# v8_engine.net
KiCad netlist of a schematic drawn in EAGLE
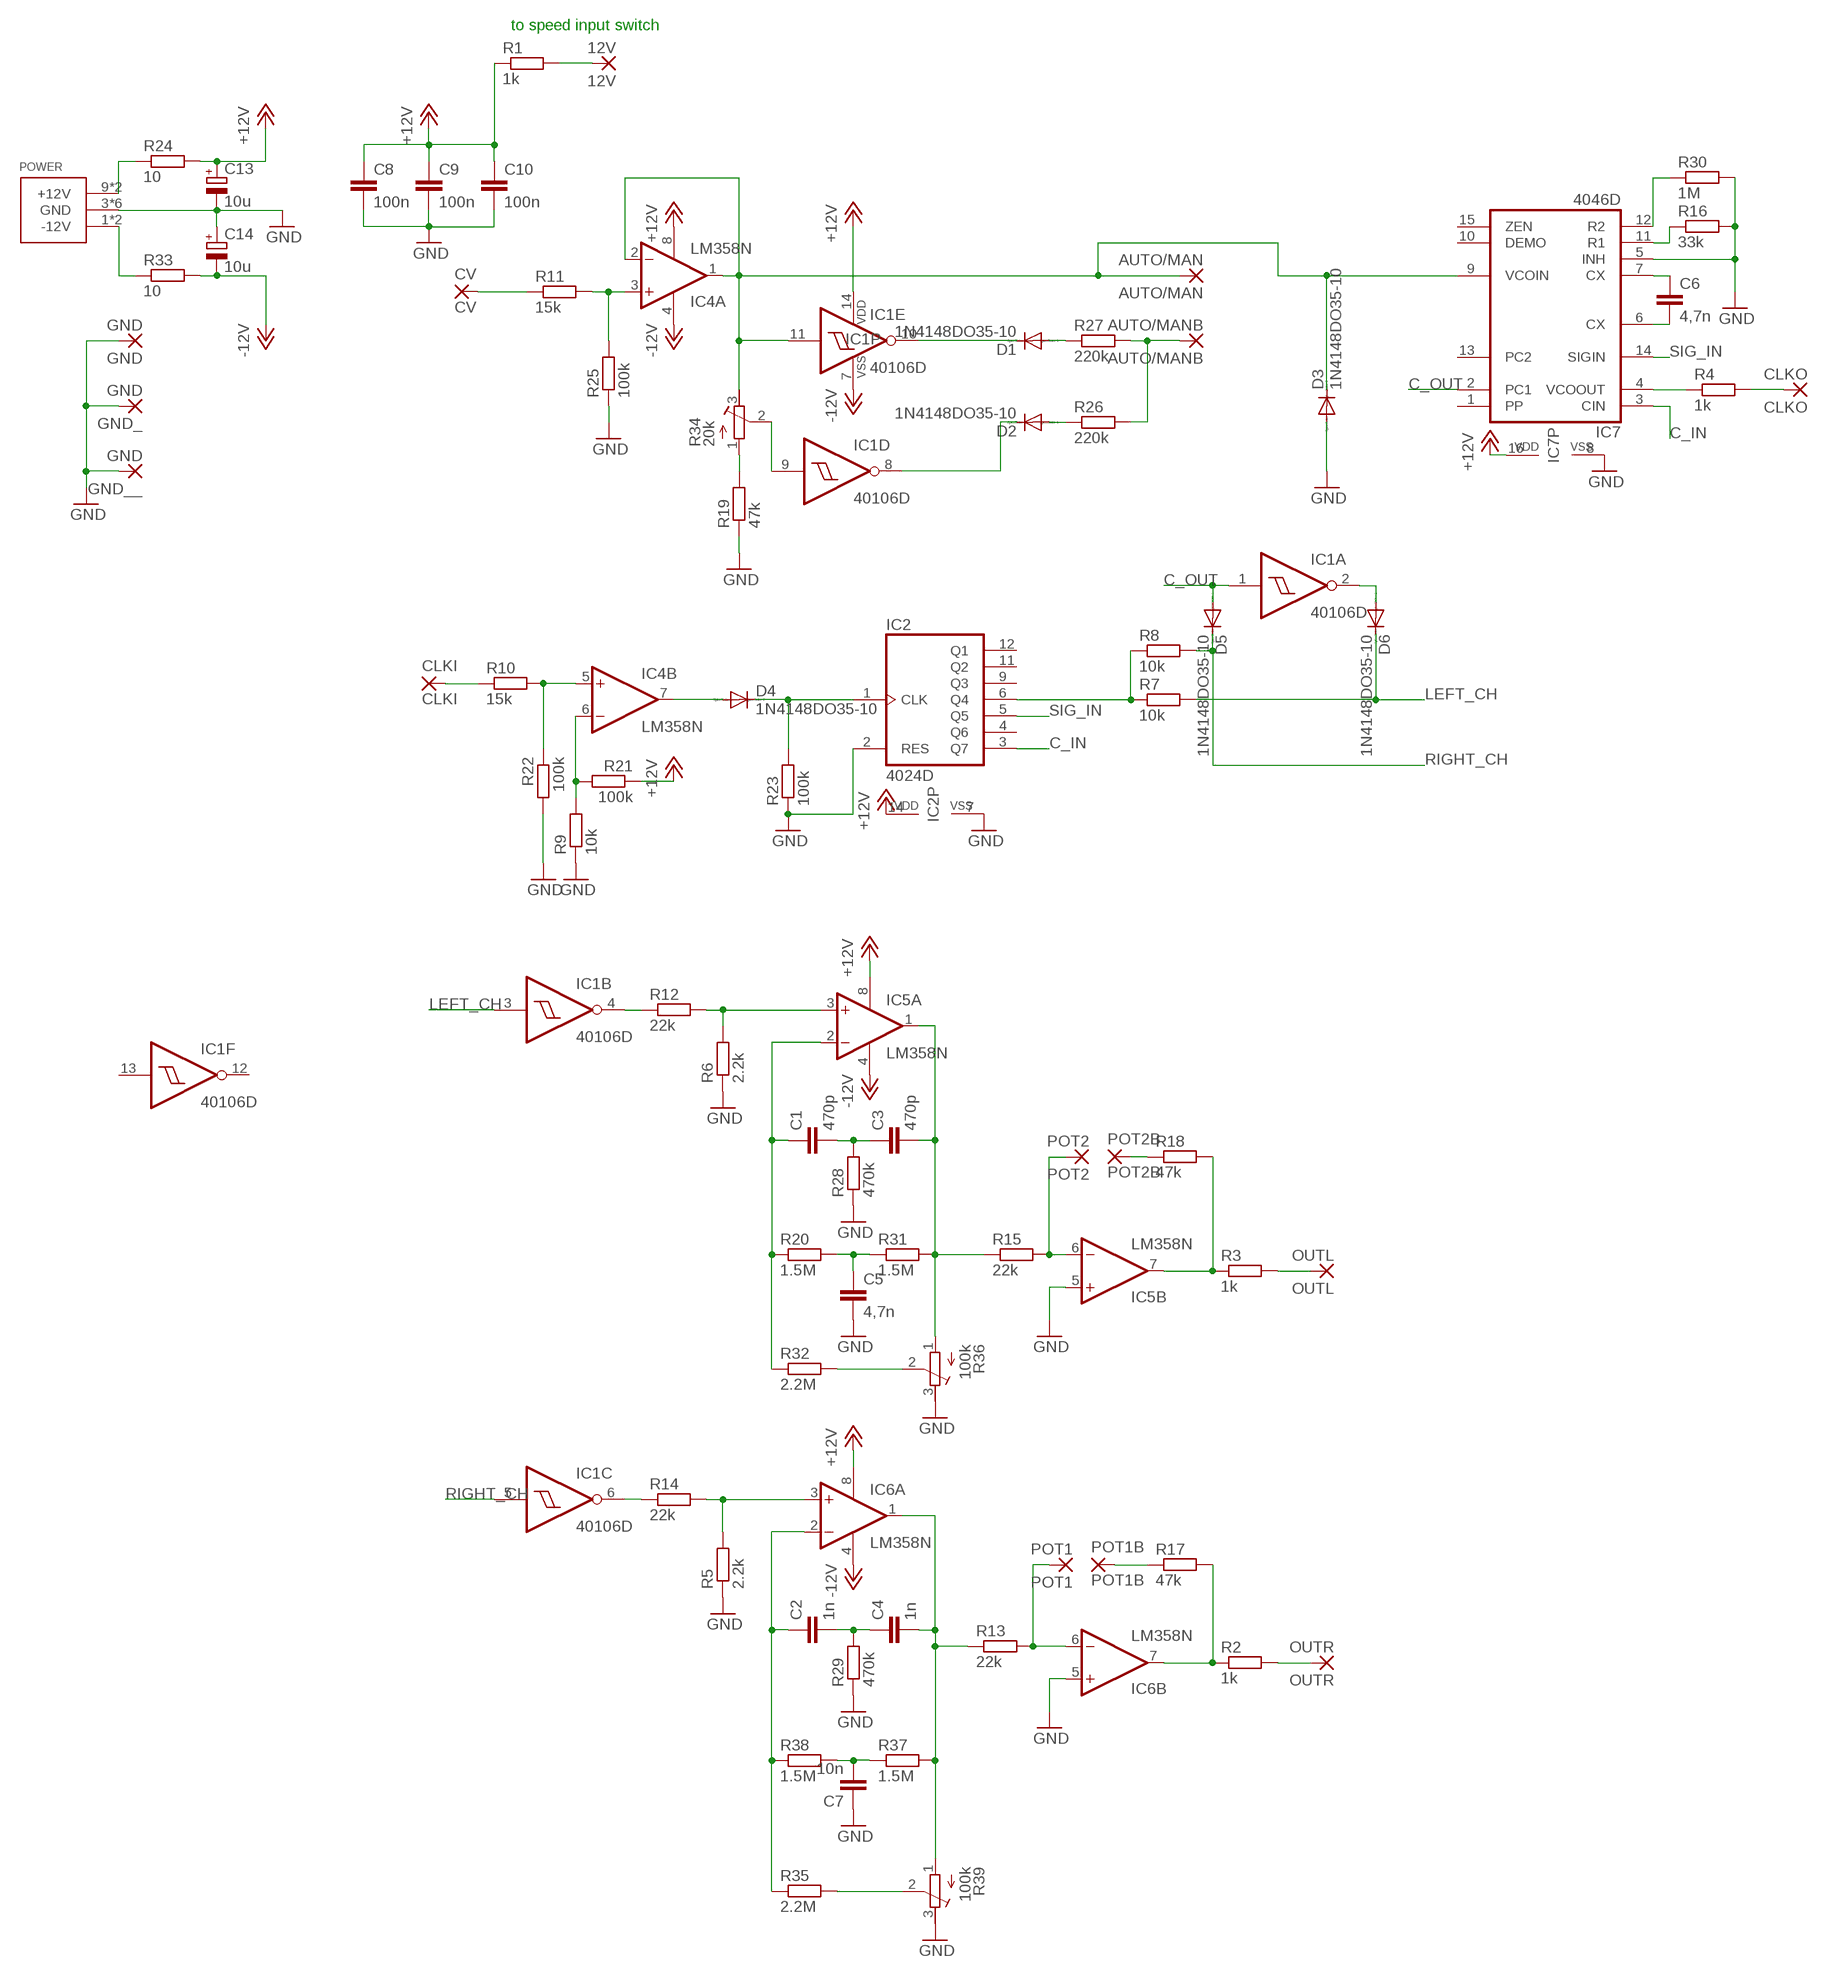
[diagram p0: schematic, sheet 1]

(export (version "E")
  (design (tool "Eeschema 10.0.6"))
  (components
    (comp (ref "12V")
      (value "12V")
      (footprint "eagle-import:1,6_0,9")
      (libsource (lib "eagle-import") (part "1,6/0,9"))
    )
    (comp (ref "AUTO/MAN")
      (value "AUTO/MAN")
      (footprint "eagle-import:1,6_0,9")
      (libsource (lib "eagle-import") (part "1,6/0,9"))
    )
    (comp (ref "AUTO/MANB")
      (value "AUTO/MANB")
      (footprint "eagle-import:1,6_0,9")
      (libsource (lib "eagle-import") (part "1,6/0,9"))
    )
    (comp (ref "C1")
      (value "470p")
      (footprint "eagle-import:C050-025X075")
      (libsource (lib "eagle-import") (part "C-EU050-025X075"))
    )
    (comp (ref "C2")
      (value "1n")
      (footprint "eagle-import:C050-025X075")
      (libsource (lib "eagle-import") (part "C-EU050-025X075"))
    )
    (comp (ref "C3")
      (value "470p")
      (footprint "eagle-import:C050-025X075")
      (libsource (lib "eagle-import") (part "C-EU050-025X075"))
    )
    (comp (ref "C4")
      (value "1n")
      (footprint "eagle-import:C050-025X075")
      (libsource (lib "eagle-import") (part "C-EU050-025X075"))
    )
    (comp (ref "C5")
      (value "4,7n")
      (footprint "eagle-import:C050-025X075")
      (libsource (lib "eagle-import") (part "C-EU050-025X075"))
    )
    (comp (ref "C6")
      (value "4,7n")
      (footprint "eagle-import:C050-025X075")
      (libsource (lib "eagle-import") (part "C-EU050-025X075"))
    )
    (comp (ref "C7")
      (value "10n")
      (footprint "eagle-import:C050-025X075")
      (libsource (lib "eagle-import") (part "C-EU050-025X075"))
    )
    (comp (ref "C8")
      (value "100n")
      (footprint "eagle-import:C050-025X075")
      (libsource (lib "eagle-import") (part "C-EU050-025X075"))
    )
    (comp (ref "C9")
      (value "100n")
      (footprint "eagle-import:C050-025X075")
      (libsource (lib "eagle-import") (part "C-EU050-025X075"))
    )
    (comp (ref "C10")
      (value "100n")
      (footprint "eagle-import:C050-025X075")
      (libsource (lib "eagle-import") (part "C-EU050-025X075"))
    )
    (comp (ref "C13")
      (value "10u")
      (footprint "eagle-import:E2,5-6")
      (libsource (lib "eagle-import") (part "CPOL-EUE2.5-6"))
    )
    (comp (ref "C14")
      (value "10u")
      (footprint "eagle-import:E2,5-6")
      (libsource (lib "eagle-import") (part "CPOL-EUE2.5-6"))
    )
    (comp (ref "CLKI")
      (value "CLKI")
      (footprint "eagle-import:1,6_0,9")
      (libsource (lib "eagle-import") (part "1,6/0,9"))
    )
    (comp (ref "CLKO")
      (value "CLKO")
      (footprint "eagle-import:1,6_0,9")
      (libsource (lib "eagle-import") (part "1,6/0,9"))
    )
    (comp (ref "CV")
      (value "CV")
      (footprint "eagle-import:1,6_0,9")
      (libsource (lib "eagle-import") (part "1,6/0,9"))
    )
    (comp (ref "D1")
      (value "1N4148DO35-10")
      (footprint "eagle-import:DO35-10")
      (libsource (lib "eagle-import") (part "1N4148DO35-10"))
    )
    (comp (ref "D2")
      (value "1N4148DO35-10")
      (footprint "eagle-import:DO35-10")
      (libsource (lib "eagle-import") (part "1N4148DO35-10"))
    )
    (comp (ref "D3")
      (value "1N4148DO35-10")
      (footprint "eagle-import:DO35-10")
      (libsource (lib "eagle-import") (part "1N4148DO35-10"))
    )
    (comp (ref "D4")
      (value "1N4148DO35-10")
      (footprint "eagle-import:DO35-10")
      (libsource (lib "eagle-import") (part "1N4148DO35-10"))
    )
    (comp (ref "D5")
      (value "1N4148DO35-10")
      (footprint "eagle-import:DO35-10")
      (libsource (lib "eagle-import") (part "1N4148DO35-10"))
    )
    (comp (ref "D6")
      (value "1N4148DO35-10")
      (footprint "eagle-import:DO35-10")
      (libsource (lib "eagle-import") (part "1N4148DO35-10"))
    )
    (comp (ref "GND")
      (value "GND")
      (footprint "eagle-import:1,6_0,9")
      (libsource (lib "eagle-import") (part "1,6/0,9"))
    )
    (comp (ref "GND_")
      (value "GND")
      (footprint "eagle-import:1,6_0,9")
      (libsource (lib "eagle-import") (part "1,6/0,9"))
    )
    (comp (ref "GND__")
      (value "GND")
      (footprint "eagle-import:1,6_0,9")
      (libsource (lib "eagle-import") (part "1,6/0,9"))
    )
    (comp (ref "IC1")
      (value "40106D")
      (footprint "eagle-import:SO14")
      (libsource (lib "eagle-import") (part "40106D"))
    )
    (comp (ref "IC2")
      (value "4024D")
      (footprint "eagle-import:SO14")
      (libsource (lib "eagle-import") (part "4024D"))
    )
    (comp (ref "IC4")
      (value "LM358N")
      (footprint "eagle-import:DIL08")
      (libsource (lib "eagle-import") (part "LM358N"))
    )
    (comp (ref "IC5")
      (value "LM358N")
      (footprint "eagle-import:DIL08")
      (libsource (lib "eagle-import") (part "LM358N"))
    )
    (comp (ref "IC6")
      (value "LM358N")
      (footprint "eagle-import:DIL08")
      (libsource (lib "eagle-import") (part "LM358N"))
    )
    (comp (ref "IC7")
      (value "4046D")
      (footprint "eagle-import:SO16")
      (libsource (lib "eagle-import") (part "4046D"))
    )
    (comp (ref "OUTL")
      (value "OUTL")
      (footprint "eagle-import:1,6_0,9")
      (libsource (lib "eagle-import") (part "1,6/0,9"))
    )
    (comp (ref "OUTR")
      (value "OUTR")
      (footprint "eagle-import:1,6_0,9")
      (libsource (lib "eagle-import") (part "1,6/0,9"))
    )
    (comp (ref "POT1")
      (value "POT1")
      (footprint "eagle-import:1,6_0,9")
      (libsource (lib "eagle-import") (part "1,6/0,9"))
    )
    (comp (ref "POT1B")
      (value "POT1B")
      (footprint "eagle-import:1,6_0,9")
      (libsource (lib "eagle-import") (part "1,6/0,9"))
    )
    (comp (ref "POT2")
      (value "POT2")
      (footprint "eagle-import:1,6_0,9")
      (libsource (lib "eagle-import") (part "1,6/0,9"))
    )
    (comp (ref "POT2B")
      (value "POT2B")
      (footprint "eagle-import:1,6_0,9")
      (libsource (lib "eagle-import") (part "1,6/0,9"))
    )
    (comp (ref "POWER")
      (value "POWER_SIMPLE10")
      (footprint "eagle-import:POWER_10")
      (libsource (lib "eagle-import") (part "POWER_SIMPLE10"))
    )
    (comp (ref "R1")
      (value "1k")
      (footprint "eagle-import:0207_10")
      (libsource (lib "eagle-import") (part "R-EU_0207/10"))
    )
    (comp (ref "R2")
      (value "1k")
      (footprint "eagle-import:0207_10")
      (libsource (lib "eagle-import") (part "R-EU_0207/10"))
    )
    (comp (ref "R3")
      (value "1k")
      (footprint "eagle-import:0207_10")
      (libsource (lib "eagle-import") (part "R-EU_0207/10"))
    )
    (comp (ref "R4")
      (value "1k")
      (footprint "eagle-import:0207_10")
      (libsource (lib "eagle-import") (part "R-EU_0207/10"))
    )
    (comp (ref "R5")
      (value "2.2k")
      (footprint "eagle-import:0207_10")
      (libsource (lib "eagle-import") (part "R-EU_0207/10"))
    )
    (comp (ref "R6")
      (value "2.2k")
      (footprint "eagle-import:0207_10")
      (libsource (lib "eagle-import") (part "R-EU_0207/10"))
    )
    (comp (ref "R7")
      (value "10k")
      (footprint "eagle-import:0207_10")
      (libsource (lib "eagle-import") (part "R-EU_0207/10"))
    )
    (comp (ref "R8")
      (value "10k")
      (footprint "eagle-import:0207_10")
      (libsource (lib "eagle-import") (part "R-EU_0207/10"))
    )
    (comp (ref "R9")
      (value "10k")
      (footprint "eagle-import:0207_10")
      (libsource (lib "eagle-import") (part "R-EU_0207/10"))
    )
    (comp (ref "R10")
      (value "15k")
      (footprint "eagle-import:0207_10")
      (libsource (lib "eagle-import") (part "R-EU_0207/10"))
    )
    (comp (ref "R11")
      (value "15k")
      (footprint "eagle-import:0207_10")
      (libsource (lib "eagle-import") (part "R-EU_0207/10"))
    )
    (comp (ref "R12")
      (value "22k")
      (footprint "eagle-import:0207_10")
      (libsource (lib "eagle-import") (part "R-EU_0207/10"))
    )
    (comp (ref "R13")
      (value "22k")
      (footprint "eagle-import:0207_10")
      (libsource (lib "eagle-import") (part "R-EU_0207/10"))
    )
    (comp (ref "R14")
      (value "22k")
      (footprint "eagle-import:0207_10")
      (libsource (lib "eagle-import") (part "R-EU_0207/10"))
    )
    (comp (ref "R15")
      (value "22k")
      (footprint "eagle-import:0207_10")
      (libsource (lib "eagle-import") (part "R-EU_0207/10"))
    )
    (comp (ref "R16")
      (value "33k")
      (footprint "eagle-import:0207_10")
      (libsource (lib "eagle-import") (part "R-EU_0207/10"))
    )
    (comp (ref "R17")
      (value "47k")
      (footprint "eagle-import:0207_10")
      (libsource (lib "eagle-import") (part "R-EU_0207/10"))
    )
    (comp (ref "R18")
      (value "47k")
      (footprint "eagle-import:0207_10")
      (libsource (lib "eagle-import") (part "R-EU_0207/10"))
    )
    (comp (ref "R19")
      (value "47k")
      (footprint "eagle-import:0207_10")
      (libsource (lib "eagle-import") (part "R-EU_0207/10"))
    )
    (comp (ref "R20")
      (value "1.5M")
      (footprint "eagle-import:0207_10")
      (libsource (lib "eagle-import") (part "R-EU_0207/10"))
    )
    (comp (ref "R21")
      (value "100k")
      (footprint "eagle-import:0207_10")
      (libsource (lib "eagle-import") (part "R-EU_0207/10"))
    )
    (comp (ref "R22")
      (value "100k")
      (footprint "eagle-import:0207_10")
      (libsource (lib "eagle-import") (part "R-EU_0207/10"))
    )
    (comp (ref "R23")
      (value "100k")
      (footprint "eagle-import:0207_10")
      (libsource (lib "eagle-import") (part "R-EU_0207/10"))
    )
    (comp (ref "R24")
      (value "10")
      (footprint "eagle-import:0207_10")
      (libsource (lib "eagle-import") (part "R-EU_0207/10"))
    )
    (comp (ref "R25")
      (value "100k")
      (footprint "eagle-import:0207_10")
      (libsource (lib "eagle-import") (part "R-EU_0207/10"))
    )
    (comp (ref "R26")
      (value "220k")
      (footprint "eagle-import:0207_10")
      (libsource (lib "eagle-import") (part "R-EU_0207/10"))
    )
    (comp (ref "R27")
      (value "220k")
      (footprint "eagle-import:0207_10")
      (libsource (lib "eagle-import") (part "R-EU_0207/10"))
    )
    (comp (ref "R28")
      (value "470k")
      (footprint "eagle-import:0207_10")
      (libsource (lib "eagle-import") (part "R-EU_0207/10"))
    )
    (comp (ref "R29")
      (value "470k")
      (footprint "eagle-import:0207_10")
      (libsource (lib "eagle-import") (part "R-EU_0207/10"))
    )
    (comp (ref "R30")
      (value "1M")
      (footprint "eagle-import:0207_10")
      (libsource (lib "eagle-import") (part "R-EU_0207/10"))
    )
    (comp (ref "R31")
      (value "1.5M")
      (footprint "eagle-import:0207_10")
      (libsource (lib "eagle-import") (part "R-EU_0207/10"))
    )
    (comp (ref "R32")
      (value "2.2M")
      (footprint "eagle-import:0207_10")
      (libsource (lib "eagle-import") (part "R-EU_0207/10"))
    )
    (comp (ref "R33")
      (value "10")
      (footprint "eagle-import:0207_10")
      (libsource (lib "eagle-import") (part "R-EU_0207/10"))
    )
    (comp (ref "R34")
      (value "20k")
      (footprint "eagle-import:RTRIM3339P")
      (libsource (lib "eagle-import") (part "R-TRIMM3339P"))
    )
    (comp (ref "R35")
      (value "2.2M")
      (footprint "eagle-import:0207_10")
      (libsource (lib "eagle-import") (part "R-EU_0207/10"))
    )
    (comp (ref "R36")
      (value "100k")
      (footprint "eagle-import:RTRIM3339P")
      (libsource (lib "eagle-import") (part "R-TRIMM3339P"))
    )
    (comp (ref "R37")
      (value "1.5M")
      (footprint "eagle-import:0207_10")
      (libsource (lib "eagle-import") (part "R-EU_0207/10"))
    )
    (comp (ref "R38")
      (value "1.5M")
      (footprint "eagle-import:0207_10")
      (libsource (lib "eagle-import") (part "R-EU_0207/10"))
    )
    (comp (ref "R39")
      (value "100k")
      (footprint "eagle-import:RTRIM3339P")
      (libsource (lib "eagle-import") (part "R-TRIMM3339P"))
    )
  )
  (nets
    (net (code "1") (name "+12V") (class "Default")
      (node (ref "C10") (pin "1") (pinfunction "1_1") (pintype "passive"))
      (node (ref "C13") (pin "+") (pinfunction "+_+") (pintype "passive"))
      (node (ref "C8") (pin "1") (pinfunction "1_1") (pintype "passive"))
      (node (ref "C9") (pin "1") (pinfunction "1_1") (pintype "passive"))
      (node (ref "IC1") (pin "14") (pinfunction "VDD_14") (pintype "power_in"))
      (node (ref "IC2") (pin "14") (pinfunction "VDD_14") (pintype "power_in"))
      (node (ref "IC4") (pin "8") (pinfunction "V+_8") (pintype "power_in"))
      (node (ref "IC5") (pin "8") (pinfunction "V+_8") (pintype "power_in"))
      (node (ref "IC6") (pin "8") (pinfunction "V+_8") (pintype "power_in"))
      (node (ref "IC7") (pin "16") (pinfunction "VDD_16") (pintype "power_in"))
      (node (ref "R1") (pin "1") (pinfunction "1_1") (pintype "passive"))
      (node (ref "R21") (pin "1") (pinfunction "1_1") (pintype "passive"))
      (node (ref "R24") (pin "2") (pinfunction "2_2") (pintype "passive"))
    )
    (net (code "2") (name "-12V") (class "Default")
      (node (ref "C14") (pin "-") (pinfunction "-_-") (pintype "passive"))
      (node (ref "IC1") (pin "7") (pinfunction "VSS_7") (pintype "power_in"))
      (node (ref "IC4") (pin "4") (pinfunction "V-_4") (pintype "power_in"))
      (node (ref "IC5") (pin "4") (pinfunction "V-_4") (pintype "power_in"))
      (node (ref "IC6") (pin "4") (pinfunction "V-_4") (pintype "power_in"))
      (node (ref "R33") (pin "2") (pinfunction "2_2") (pintype "passive"))
    )
    (net (code "3") (name "/C_IN") (class "Default")
      (node (ref "IC2") (pin "3") (pinfunction "Q7_3") (pintype "output"))
      (node (ref "IC7") (pin "3") (pinfunction "CIN_3") (pintype "input"))
    )
    (net (code "4") (name "/C_OUT") (class "Default")
      (node (ref "D5") (pin "A") (pinfunction "A_A") (pintype "passive"))
      (node (ref "IC1") (pin "1") (pinfunction "I_1") (pintype "input"))
      (node (ref "IC7") (pin "2") (pinfunction "PC1_2") (pintype "output"))
    )
    (net (code "5") (name "/LEFT_CH") (class "Default")
      (node (ref "D6") (pin "C") (pinfunction "C_C") (pintype "passive"))
      (node (ref "IC1") (pin "3") (pinfunction "I_3") (pintype "input"))
      (node (ref "R7") (pin "2") (pinfunction "2_2") (pintype "passive"))
    )
    (net (code "6") (name "/RIGHT_CH") (class "Default")
      (node (ref "D5") (pin "C") (pinfunction "C_C") (pintype "passive"))
      (node (ref "IC1") (pin "5") (pinfunction "I_5") (pintype "input"))
      (node (ref "R8") (pin "2") (pinfunction "2_2") (pintype "passive"))
    )
    (net (code "7") (name "/SIG_IN") (class "Default")
      (node (ref "IC2") (pin "5") (pinfunction "Q5_5") (pintype "output"))
      (node (ref "IC7") (pin "14") (pinfunction "SIGIN_14") (pintype "input"))
    )
    (net (code "8") (name "GND") (class "Default")
      (node (ref "C10") (pin "2") (pinfunction "2_2") (pintype "passive"))
      (node (ref "C13") (pin "-") (pinfunction "-_-") (pintype "passive"))
      (node (ref "C14") (pin "+") (pinfunction "+_+") (pintype "passive"))
      (node (ref "C5") (pin "2") (pinfunction "2_2") (pintype "passive"))
      (node (ref "C7") (pin "1") (pinfunction "1_1") (pintype "passive"))
      (node (ref "C8") (pin "2") (pinfunction "2_2") (pintype "passive"))
      (node (ref "C9") (pin "2") (pinfunction "2_2") (pintype "passive"))
      (node (ref "D3") (pin "A") (pinfunction "A_A") (pintype "passive"))
      (node (ref "GND") (pin "1") (pinfunction "P_1") (pintype "passive"))
      (node (ref "GND_") (pin "1") (pinfunction "P_1") (pintype "passive"))
      (node (ref "GND__") (pin "1") (pinfunction "P_1") (pintype "passive"))
      (node (ref "IC2") (pin "2") (pinfunction "RES_2") (pintype "input"))
      (node (ref "IC2") (pin "7") (pinfunction "VSS_7") (pintype "power_in"))
      (node (ref "IC5") (pin "5") (pinfunction "+IN_5") (pintype "input"))
      (node (ref "IC6") (pin "5") (pinfunction "+IN_5") (pintype "input"))
      (node (ref "IC7") (pin "5") (pinfunction "INH_5") (pintype "input"))
      (node (ref "IC7") (pin "8") (pinfunction "VSS_8") (pintype "power_in"))
      (node (ref "POWER") (pin "3") (pinfunction "GND_3") (pintype "bidirectional"))
      (node (ref "POWER") (pin "4") (pinfunction "GND_4") (pintype "bidirectional"))
      (node (ref "POWER") (pin "5") (pinfunction "GND_5") (pintype "bidirectional"))
      (node (ref "POWER") (pin "6") (pinfunction "GND_6") (pintype "bidirectional"))
      (node (ref "POWER") (pin "7") (pinfunction "GND_7") (pintype "bidirectional"))
      (node (ref "POWER") (pin "8") (pinfunction "GND_8") (pintype "bidirectional"))
      (node (ref "R16") (pin "2") (pinfunction "2_2") (pintype "passive"))
      (node (ref "R19") (pin "1") (pinfunction "1_1") (pintype "passive"))
      (node (ref "R22") (pin "2") (pinfunction "2_2") (pintype "passive"))
      (node (ref "R23") (pin "1") (pinfunction "1_1") (pintype "passive"))
      (node (ref "R25") (pin "1") (pinfunction "1_1") (pintype "passive"))
      (node (ref "R28") (pin "1") (pinfunction "1_1") (pintype "passive"))
      (node (ref "R29") (pin "1") (pinfunction "1_1") (pintype "passive"))
      (node (ref "R30") (pin "2") (pinfunction "2_2") (pintype "passive"))
      (node (ref "R36") (pin "3") (pinfunction "E_3") (pintype "passive"))
      (node (ref "R39") (pin "3") (pinfunction "E_3") (pintype "passive"))
      (node (ref "R5") (pin "1") (pinfunction "1_1") (pintype "passive"))
      (node (ref "R6") (pin "1") (pinfunction "1_1") (pintype "passive"))
      (node (ref "R9") (pin "1") (pinfunction "1_1") (pintype "passive"))
    )
    (net (code "9") (name "Net-(12V-P)") (class "Default")
      (node (ref "12V") (pin "1") (pinfunction "P_1") (pintype "passive"))
      (node (ref "R1") (pin "2") (pinfunction "2_2") (pintype "passive"))
    )
    (net (code "10") (name "Net-(AUTO/MAN-P)") (class "Default")
      (node (ref "AUTO/MAN") (pin "1") (pinfunction "P_1") (pintype "passive"))
      (node (ref "D3") (pin "C") (pinfunction "C_C") (pintype "passive"))
      (node (ref "IC1") (pin "11") (pinfunction "I_11") (pintype "input"))
      (node (ref "IC4") (pin "1") (pinfunction "OUT_1") (pintype "output"))
      (node (ref "IC4") (pin "2") (pinfunction "-IN_2") (pintype "input"))
      (node (ref "IC7") (pin "9") (pinfunction "VCOIN_9") (pintype "input"))
      (node (ref "R34") (pin "3") (pinfunction "E_3") (pintype "passive"))
    )
    (net (code "11") (name "Net-(AUTO/MANB-P)") (class "Default")
      (node (ref "AUTO/MANB") (pin "1") (pinfunction "P_1") (pintype "passive"))
      (node (ref "R26") (pin "2") (pinfunction "2_2") (pintype "passive"))
      (node (ref "R27") (pin "2") (pinfunction "2_2") (pintype "passive"))
    )
    (net (code "12") (name "Net-(C1-Pad2)") (class "Default")
      (node (ref "C1") (pin "2") (pinfunction "2_2") (pintype "passive"))
      (node (ref "C3") (pin "1") (pinfunction "1_1") (pintype "passive"))
      (node (ref "R28") (pin "2") (pinfunction "2_2") (pintype "passive"))
    )
    (net (code "13") (name "Net-(C2-Pad2)") (class "Default")
      (node (ref "C2") (pin "2") (pinfunction "2_2") (pintype "passive"))
      (node (ref "C4") (pin "1") (pinfunction "1_1") (pintype "passive"))
      (node (ref "R29") (pin "2") (pinfunction "2_2") (pintype "passive"))
    )
    (net (code "14") (name "Net-(C5-Pad1)") (class "Default")
      (node (ref "C5") (pin "1") (pinfunction "1_1") (pintype "passive"))
      (node (ref "R20") (pin "2") (pinfunction "2_2") (pintype "passive"))
      (node (ref "R31") (pin "1") (pinfunction "1_1") (pintype "passive"))
    )
    (net (code "15") (name "Net-(C6-Pad1)") (class "Default")
      (node (ref "C6") (pin "1") (pinfunction "1_1") (pintype "passive"))
      (node (ref "IC7") (pin "7") (pinfunction "CX_7") (pintype "input"))
    )
    (net (code "16") (name "Net-(C6-Pad2)") (class "Default")
      (node (ref "C6") (pin "2") (pinfunction "2_2") (pintype "passive"))
      (node (ref "IC7") (pin "6") (pinfunction "CX_6") (pintype "input"))
    )
    (net (code "17") (name "Net-(C7-Pad2)") (class "Default")
      (node (ref "C7") (pin "2") (pinfunction "2_2") (pintype "passive"))
      (node (ref "R37") (pin "1") (pinfunction "1_1") (pintype "passive"))
      (node (ref "R38") (pin "2") (pinfunction "2_2") (pintype "passive"))
    )
    (net (code "18") (name "Net-(CLKI-P)") (class "Default")
      (node (ref "CLKI") (pin "1") (pinfunction "P_1") (pintype "passive"))
      (node (ref "R10") (pin "1") (pinfunction "1_1") (pintype "passive"))
    )
    (net (code "19") (name "Net-(CLKO-P)") (class "Default")
      (node (ref "CLKO") (pin "1") (pinfunction "P_1") (pintype "passive"))
      (node (ref "R4") (pin "2") (pinfunction "2_2") (pintype "passive"))
    )
    (net (code "20") (name "Net-(CV-P)") (class "Default")
      (node (ref "CV") (pin "1") (pinfunction "P_1") (pintype "passive"))
      (node (ref "R11") (pin "1") (pinfunction "1_1") (pintype "passive"))
    )
    (net (code "21") (name "Net-(D1-PadA)") (class "Default")
      (node (ref "D1") (pin "A") (pinfunction "A_A") (pintype "passive"))
      (node (ref "R27") (pin "1") (pinfunction "1_1") (pintype "passive"))
    )
    (net (code "22") (name "Net-(D2-PadA)") (class "Default")
      (node (ref "D2") (pin "A") (pinfunction "A_A") (pintype "passive"))
      (node (ref "R26") (pin "1") (pinfunction "1_1") (pintype "passive"))
    )
    (net (code "23") (name "Net-(IC1A-O)") (class "Default")
      (node (ref "D6") (pin "A") (pinfunction "A_A") (pintype "passive"))
      (node (ref "IC1") (pin "2") (pinfunction "O_2") (pintype "output"))
    )
    (net (code "24") (name "Net-(IC1B-O)") (class "Default")
      (node (ref "IC1") (pin "4") (pinfunction "O_4") (pintype "output"))
      (node (ref "R12") (pin "1") (pinfunction "1_1") (pintype "passive"))
    )
    (net (code "25") (name "Net-(IC1C-O)") (class "Default")
      (node (ref "IC1") (pin "6") (pinfunction "O_6") (pintype "output"))
      (node (ref "R14") (pin "1") (pinfunction "1_1") (pintype "passive"))
    )
    (net (code "26") (name "Net-(IC1D-I)") (class "Default")
      (node (ref "IC1") (pin "9") (pinfunction "I_9") (pintype "input"))
      (node (ref "R34") (pin "2") (pinfunction "S_2") (pintype "passive"))
    )
    (net (code "27") (name "Net-(IC1D-O)") (class "Default")
      (node (ref "D2") (pin "C") (pinfunction "C_C") (pintype "passive"))
      (node (ref "IC1") (pin "8") (pinfunction "O_8") (pintype "output"))
    )
    (net (code "28") (name "Net-(IC1E-O)") (class "Default")
      (node (ref "D1") (pin "C") (pinfunction "C_C") (pintype "passive"))
      (node (ref "IC1") (pin "10") (pinfunction "O_10") (pintype "output"))
    )
    (net (code "29") (name "Net-(IC2A-CLK)") (class "Default")
      (node (ref "D4") (pin "C") (pinfunction "C_C") (pintype "passive"))
      (node (ref "IC2") (pin "1") (pinfunction "CLK_1") (pintype "input"))
      (node (ref "R23") (pin "2") (pinfunction "2_2") (pintype "passive"))
    )
    (net (code "30") (name "Net-(IC2A-Q4)") (class "Default")
      (node (ref "IC2") (pin "6") (pinfunction "Q4_6") (pintype "output"))
      (node (ref "R7") (pin "1") (pinfunction "1_1") (pintype "passive"))
      (node (ref "R8") (pin "1") (pinfunction "1_1") (pintype "passive"))
    )
    (net (code "31") (name "Net-(IC4A-+IN)") (class "Default")
      (node (ref "IC4") (pin "3") (pinfunction "+IN_3") (pintype "input"))
      (node (ref "R11") (pin "2") (pinfunction "2_2") (pintype "passive"))
      (node (ref "R25") (pin "2") (pinfunction "2_2") (pintype "passive"))
    )
    (net (code "32") (name "Net-(IC4B-+IN)") (class "Default")
      (node (ref "IC4") (pin "5") (pinfunction "+IN_5") (pintype "input"))
      (node (ref "R10") (pin "2") (pinfunction "2_2") (pintype "passive"))
      (node (ref "R22") (pin "1") (pinfunction "1_1") (pintype "passive"))
    )
    (net (code "33") (name "Net-(IC4B--IN)") (class "Default")
      (node (ref "IC4") (pin "6") (pinfunction "-IN_6") (pintype "input"))
      (node (ref "R21") (pin "2") (pinfunction "2_2") (pintype "passive"))
      (node (ref "R9") (pin "2") (pinfunction "2_2") (pintype "passive"))
    )
    (net (code "34") (name "Net-(IC4B-OUT)") (class "Default")
      (node (ref "D4") (pin "A") (pinfunction "A_A") (pintype "passive"))
      (node (ref "IC4") (pin "7") (pinfunction "OUT_7") (pintype "output"))
    )
    (net (code "35") (name "Net-(IC5A-+IN)") (class "Default")
      (node (ref "IC5") (pin "3") (pinfunction "+IN_3") (pintype "input"))
      (node (ref "R12") (pin "2") (pinfunction "2_2") (pintype "passive"))
      (node (ref "R6") (pin "2") (pinfunction "2_2") (pintype "passive"))
    )
    (net (code "36") (name "Net-(IC5A--IN)") (class "Default")
      (node (ref "C1") (pin "1") (pinfunction "1_1") (pintype "passive"))
      (node (ref "IC5") (pin "2") (pinfunction "-IN_2") (pintype "input"))
      (node (ref "R20") (pin "1") (pinfunction "1_1") (pintype "passive"))
      (node (ref "R32") (pin "1") (pinfunction "1_1") (pintype "passive"))
    )
    (net (code "37") (name "Net-(IC5A-OUT)") (class "Default")
      (node (ref "C3") (pin "2") (pinfunction "2_2") (pintype "passive"))
      (node (ref "IC5") (pin "1") (pinfunction "OUT_1") (pintype "output"))
      (node (ref "R15") (pin "1") (pinfunction "1_1") (pintype "passive"))
      (node (ref "R31") (pin "2") (pinfunction "2_2") (pintype "passive"))
      (node (ref "R36") (pin "1") (pinfunction "A_1") (pintype "passive"))
    )
    (net (code "38") (name "Net-(IC5B--IN)") (class "Default")
      (node (ref "IC5") (pin "6") (pinfunction "-IN_6") (pintype "input"))
      (node (ref "POT2") (pin "1") (pinfunction "P_1") (pintype "passive"))
      (node (ref "R15") (pin "2") (pinfunction "2_2") (pintype "passive"))
    )
    (net (code "39") (name "Net-(IC5B-OUT)") (class "Default")
      (node (ref "IC5") (pin "7") (pinfunction "OUT_7") (pintype "output"))
      (node (ref "R18") (pin "2") (pinfunction "2_2") (pintype "passive"))
      (node (ref "R3") (pin "1") (pinfunction "1_1") (pintype "passive"))
    )
    (net (code "40") (name "Net-(IC6A-+IN)") (class "Default")
      (node (ref "IC6") (pin "3") (pinfunction "+IN_3") (pintype "input"))
      (node (ref "R14") (pin "2") (pinfunction "2_2") (pintype "passive"))
      (node (ref "R5") (pin "2") (pinfunction "2_2") (pintype "passive"))
    )
    (net (code "41") (name "Net-(IC6A--IN)") (class "Default")
      (node (ref "C2") (pin "1") (pinfunction "1_1") (pintype "passive"))
      (node (ref "IC6") (pin "2") (pinfunction "-IN_2") (pintype "input"))
      (node (ref "R35") (pin "1") (pinfunction "1_1") (pintype "passive"))
      (node (ref "R38") (pin "1") (pinfunction "1_1") (pintype "passive"))
    )
    (net (code "42") (name "Net-(IC6A-OUT)") (class "Default")
      (node (ref "C4") (pin "2") (pinfunction "2_2") (pintype "passive"))
      (node (ref "IC6") (pin "1") (pinfunction "OUT_1") (pintype "output"))
      (node (ref "R13") (pin "1") (pinfunction "1_1") (pintype "passive"))
      (node (ref "R37") (pin "2") (pinfunction "2_2") (pintype "passive"))
      (node (ref "R39") (pin "1") (pinfunction "A_1") (pintype "passive"))
    )
    (net (code "43") (name "Net-(IC6B--IN)") (class "Default")
      (node (ref "IC6") (pin "6") (pinfunction "-IN_6") (pintype "input"))
      (node (ref "POT1") (pin "1") (pinfunction "P_1") (pintype "passive"))
      (node (ref "R13") (pin "2") (pinfunction "2_2") (pintype "passive"))
    )
    (net (code "44") (name "Net-(IC6B-OUT)") (class "Default")
      (node (ref "IC6") (pin "7") (pinfunction "OUT_7") (pintype "output"))
      (node (ref "R17") (pin "2") (pinfunction "2_2") (pintype "passive"))
      (node (ref "R2") (pin "1") (pinfunction "1_1") (pintype "passive"))
    )
    (net (code "45") (name "Net-(IC7A-R1)") (class "Default")
      (node (ref "IC7") (pin "11") (pinfunction "R1_11") (pintype "input"))
      (node (ref "R16") (pin "1") (pinfunction "1_1") (pintype "passive"))
    )
    (net (code "46") (name "Net-(IC7A-R2)") (class "Default")
      (node (ref "IC7") (pin "12") (pinfunction "R2_12") (pintype "input"))
      (node (ref "R30") (pin "1") (pinfunction "1_1") (pintype "passive"))
    )
    (net (code "47") (name "Net-(IC7A-VCOOUT)") (class "Default")
      (node (ref "IC7") (pin "4") (pinfunction "VCOOUT_4") (pintype "output"))
      (node (ref "R4") (pin "1") (pinfunction "1_1") (pintype "passive"))
    )
    (net (code "48") (name "Net-(OUTL-P)") (class "Default")
      (node (ref "OUTL") (pin "1") (pinfunction "P_1") (pintype "passive"))
      (node (ref "R3") (pin "2") (pinfunction "2_2") (pintype "passive"))
    )
    (net (code "49") (name "Net-(OUTR-P)") (class "Default")
      (node (ref "OUTR") (pin "1") (pinfunction "P_1") (pintype "passive"))
      (node (ref "R2") (pin "2") (pinfunction "2_2") (pintype "passive"))
    )
    (net (code "50") (name "Net-(POT1B-P)") (class "Default")
      (node (ref "POT1B") (pin "1") (pinfunction "P_1") (pintype "passive"))
      (node (ref "R17") (pin "1") (pinfunction "1_1") (pintype "passive"))
    )
    (net (code "51") (name "Net-(POT2B-P)") (class "Default")
      (node (ref "POT2B") (pin "1") (pinfunction "P_1") (pintype "passive"))
      (node (ref "R18") (pin "1") (pinfunction "1_1") (pintype "passive"))
    )
    (net (code "52") (name "Net-(POWER-+12V-Pad10)") (class "Default")
      (node (ref "POWER") (pin "10") (pinfunction "+12V_10") (pintype "bidirectional"))
      (node (ref "POWER") (pin "9") (pinfunction "+12V_9") (pintype "bidirectional"))
      (node (ref "R24") (pin "1") (pinfunction "1_1") (pintype "passive"))
    )
    (net (code "53") (name "Net-(POWER--12V-Pad1)") (class "Default")
      (node (ref "POWER") (pin "1") (pinfunction "-12V_1") (pintype "bidirectional"))
      (node (ref "POWER") (pin "2") (pinfunction "-12V_2") (pintype "bidirectional"))
      (node (ref "R33") (pin "1") (pinfunction "1_1") (pintype "passive"))
    )
    (net (code "54") (name "Net-(R34-A)") (class "Default")
      (node (ref "R19") (pin "2") (pinfunction "2_2") (pintype "passive"))
      (node (ref "R34") (pin "1") (pinfunction "A_1") (pintype "passive"))
    )
    (net (code "55") (name "Net-(R36-S)") (class "Default")
      (node (ref "R32") (pin "2") (pinfunction "2_2") (pintype "passive"))
      (node (ref "R36") (pin "2") (pinfunction "S_2") (pintype "passive"))
    )
    (net (code "56") (name "Net-(R39-S)") (class "Default")
      (node (ref "R35") (pin "2") (pinfunction "2_2") (pintype "passive"))
      (node (ref "R39") (pin "2") (pinfunction "S_2") (pintype "passive"))
    )
    (net (code "57") (name "unconnected-(IC1F-I-Pad13)") (class "Default")
      (node (ref "IC1") (pin "13") (pinfunction "I_13") (pintype "input"))
    )
    (net (code "58") (name "unconnected-(IC1F-O-Pad12)") (class "Default")
      (node (ref "IC1") (pin "12") (pinfunction "O_12") (pintype "output"))
    )
    (net (code "59") (name "unconnected-(IC2A-Q1-Pad12)") (class "Default")
      (node (ref "IC2") (pin "12") (pinfunction "Q1_12") (pintype "output"))
    )
    (net (code "60") (name "unconnected-(IC2A-Q2-Pad11)") (class "Default")
      (node (ref "IC2") (pin "11") (pinfunction "Q2_11") (pintype "output"))
    )
    (net (code "61") (name "unconnected-(IC2A-Q3-Pad9)") (class "Default")
      (node (ref "IC2") (pin "9") (pinfunction "Q3_9") (pintype "output"))
    )
    (net (code "62") (name "unconnected-(IC2A-Q6-Pad4)") (class "Default")
      (node (ref "IC2") (pin "4") (pinfunction "Q6_4") (pintype "output"))
    )
    (net (code "63") (name "unconnected-(IC7A-DEMO-Pad10)") (class "Default")
      (node (ref "IC7") (pin "10") (pinfunction "DEMO_10") (pintype "output"))
    )
    (net (code "64") (name "unconnected-(IC7A-PC2-Pad13)") (class "Default")
      (node (ref "IC7") (pin "13") (pinfunction "PC2_13") (pintype "output"))
    )
    (net (code "65") (name "unconnected-(IC7A-PP-Pad1)") (class "Default")
      (node (ref "IC7") (pin "1") (pinfunction "PP_1") (pintype "output"))
    )
    (net (code "66") (name "unconnected-(IC7A-ZEN-Pad15)") (class "Default")
      (node (ref "IC7") (pin "15") (pinfunction "ZEN_15") (pintype "input"))
    )
  )
)
